# ASIC-Board.net
KiCad netlist of a schematic drawn in Altium Designer
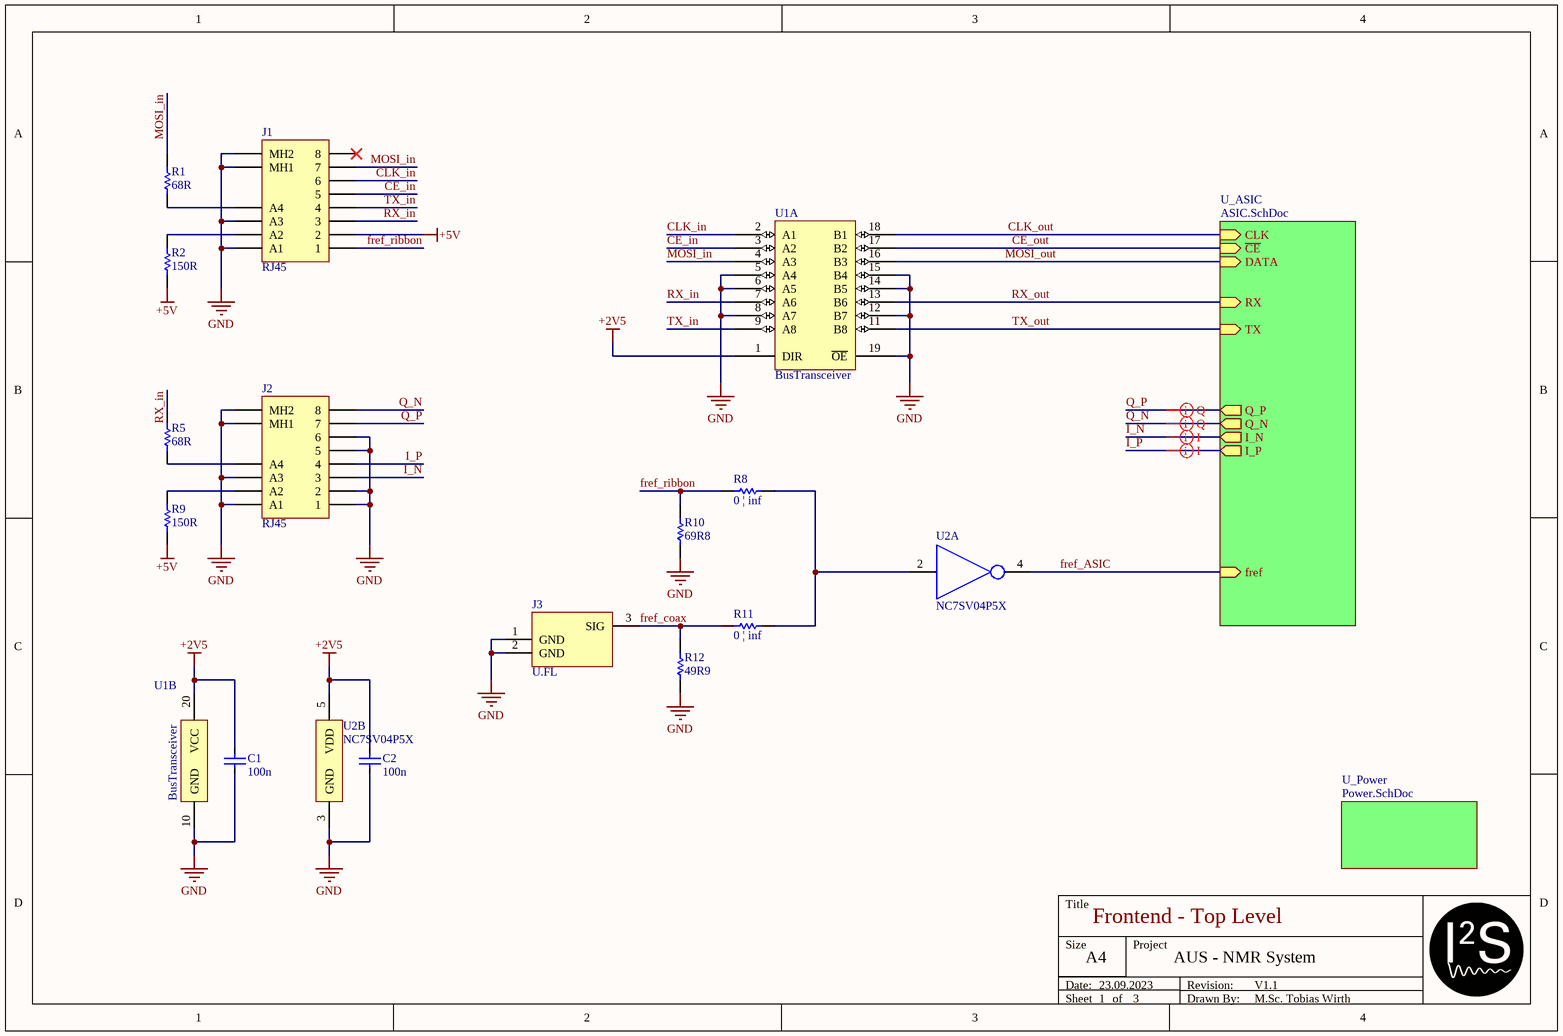
[diagram p0: ASIC-Board.SchDoc]

(export (version "E")
  (design (tool "Eeschema 10.0.6"))
  (components
    (comp (ref "C1") (value "100n") (footprint "CAP_0402") (libsource (lib "IIS-Lib_TW") (part "Cap")))
    (comp (ref "C2") (value "100n") (footprint "CAP_0402") (libsource (lib "IIS-Lib_TW") (part "Cap")))
    (comp (ref "J1")
      (value "RJ45")
      (footprint "RJ45 - RJE3A1880412")
      (description "Ethernet Connectors RJ45 SMT")
      (libsource (lib "IIS-Lib_TW") (part "RJ45"))
    )
    (comp (ref "J2")
      (value "RJ45")
      (footprint "RJ45 - RJE3A1880412")
      (description "Ethernet Connectors RJ45 SMT")
      (libsource (lib "IIS-Lib_TW") (part "RJ45"))
    )
    (comp (ref "J3") (value "U.FL") (footprint "U.FL") (libsource (lib "IIS-Lib_TW") (part "U.FL")))
    (comp (ref "R1") (value "68R") (footprint "RES_0603") (libsource (lib "IIS-Lib_TW") (part "Res")))
    (comp (ref "R2") (value "150R") (footprint "RES_0603") (libsource (lib "IIS-Lib_TW") (part "Res")))
    (comp (ref "R5") (value "68R") (footprint "RES_0603") (libsource (lib "IIS-Lib_TW") (part "Res")))
    (comp (ref "R8") (value "0 ¦ inf") (footprint "RES_0402") (libsource (lib "IIS-Lib_TW") (part "Res")))
    (comp (ref "R9") (value "150R") (footprint "RES_0603") (libsource (lib "IIS-Lib_TW") (part "Res")))
    (comp (ref "R10") (value "69R8") (footprint "RES_0402") (libsource (lib "IIS-Lib_TW") (part "Res")))
    (comp (ref "R11") (value "0 ¦ inf") (footprint "RES_0402") (libsource (lib "IIS-Lib_TW") (part "Res")))
    (comp (ref "R12") (value "49R9") (footprint "RES_0402") (libsource (lib "IIS-Lib_TW") (part "Res")))
    (comp (ref "U1")
      (value "BusTransceiver")
      (footprint "TSSOP-20")
      (libsource (lib "IIS-Lib_TW") (part "74LVC245A"))
    )
    (comp (ref "U2")
      (value "NC7SV04P5X")
      (footprint "SOT23-65P210X110-5N")
      (libsource (lib "IIS-Lib_TW") (part "NC7SV04P5X"))
    )
  )
  (nets
    (net (code "1") (name "+2V5") (class "Default")
      (node (ref "C1") (pin "1") (pinfunction "1_1") (pintype "passive"))
      (node (ref "C2") (pin "1") (pinfunction "1_1") (pintype "passive"))
      (node (ref "U1") (pin "1") (pinfunction "DIR_1") (pintype "passive"))
      (node (ref "U1") (pin "20") (pinfunction "VCC_20") (pintype "passive"))
      (node (ref "U2") (pin "5") (pinfunction "VDD_5") (pintype "passive"))
    )
    (net (code "2") (name "+5V") (class "Default")
      (node (ref "J1") (pin "2") (pinfunction "2_2") (pintype "passive"))
      (node (ref "R2") (pin "2") (pinfunction "2_2") (pintype "passive"))
      (node (ref "R9") (pin "2") (pinfunction "2_2") (pintype "passive"))
    )
    (net (code "3") (name "/CE_in") (class "Default")
      (node (ref "J1") (pin "5") (pinfunction "5_5") (pintype "passive"))
      (node (ref "U1") (pin "3") (pinfunction "A2_3") (pintype "bidirectional"))
    )
    (net (code "4") (name "/CE_out") (class "Default")
      (node (ref "U1") (pin "17") (pinfunction "B2_17") (pintype "bidirectional"))
    )
    (net (code "5") (name "/CLK_in") (class "Default")
      (node (ref "J1") (pin "6") (pinfunction "6_6") (pintype "passive"))
      (node (ref "U1") (pin "2") (pinfunction "A1_2") (pintype "bidirectional"))
    )
    (net (code "6") (name "/CLK_out") (class "Default")
      (node (ref "U1") (pin "18") (pinfunction "B1_18") (pintype "bidirectional"))
    )
    (net (code "7") (name "/I_N") (class "Default")
      (node (ref "J2") (pin "3") (pinfunction "3_3") (pintype "passive"))
    )
    (net (code "8") (name "/I_P") (class "Default")
      (node (ref "J2") (pin "4") (pinfunction "4_4") (pintype "passive"))
    )
    (net (code "9") (name "/MOSI_in") (class "Default")
      (node (ref "J1") (pin "7") (pinfunction "7_7") (pintype "passive"))
      (node (ref "R1") (pin "1") (pinfunction "1_1") (pintype "passive"))
      (node (ref "U1") (pin "4") (pinfunction "A3_4") (pintype "bidirectional"))
    )
    (net (code "10") (name "/MOSI_out") (class "Default")
      (node (ref "U1") (pin "16") (pinfunction "B3_16") (pintype "bidirectional"))
    )
    (net (code "11") (name "/Q_N") (class "Default")
      (node (ref "J2") (pin "8") (pinfunction "8_8") (pintype "passive"))
    )
    (net (code "12") (name "/Q_P") (class "Default")
      (node (ref "J2") (pin "7") (pinfunction "7_7") (pintype "passive"))
    )
    (net (code "13") (name "/RX_in") (class "Default")
      (node (ref "J1") (pin "3") (pinfunction "3_3") (pintype "passive"))
      (node (ref "R5") (pin "1") (pinfunction "1_1") (pintype "passive"))
      (node (ref "U1") (pin "7") (pinfunction "A6_7") (pintype "bidirectional"))
    )
    (net (code "14") (name "/RX_out") (class "Default")
      (node (ref "U1") (pin "13") (pinfunction "B6_13") (pintype "bidirectional"))
    )
    (net (code "15") (name "/TX_in") (class "Default")
      (node (ref "J1") (pin "4") (pinfunction "4_4") (pintype "passive"))
      (node (ref "U1") (pin "9") (pinfunction "A8_9") (pintype "bidirectional"))
    )
    (net (code "16") (name "/TX_out") (class "Default")
      (node (ref "U1") (pin "11") (pinfunction "B8_11") (pintype "bidirectional"))
    )
    (net (code "17") (name "/fref_ASIC") (class "Default")
      (node (ref "U2") (pin "4") (pinfunction "4_4") (pintype "passive"))
    )
    (net (code "18") (name "/fref_coax") (class "Default")
      (node (ref "J3") (pin "3") (pinfunction "SIG_3") (pintype "passive"))
      (node (ref "R11") (pin "2") (pinfunction "2_2") (pintype "passive"))
      (node (ref "R12") (pin "2") (pinfunction "2_2") (pintype "passive"))
    )
    (net (code "19") (name "/fref_ribbon") (class "Default")
      (node (ref "J1") (pin "1") (pinfunction "1_1") (pintype "passive"))
      (node (ref "R10") (pin "2") (pinfunction "2_2") (pintype "passive"))
      (node (ref "R8") (pin "2") (pinfunction "2_2") (pintype "passive"))
    )
    (net (code "20") (name "GND") (class "Default")
      (node (ref "C1") (pin "2") (pinfunction "2_2") (pintype "passive"))
      (node (ref "C2") (pin "2") (pinfunction "2_2") (pintype "passive"))
      (node (ref "J1") (pin "A1") (pinfunction "A1_A1") (pintype "passive"))
      (node (ref "J1") (pin "A3") (pinfunction "A3_A3") (pintype "passive"))
      (node (ref "J1") (pin "MH1") (pinfunction "MH1_MH1") (pintype "passive"))
      (node (ref "J1") (pin "MH2") (pinfunction "MH2_MH2") (pintype "passive"))
      (node (ref "J2") (pin "1") (pinfunction "1_1") (pintype "passive"))
      (node (ref "J2") (pin "2") (pinfunction "2_2") (pintype "passive"))
      (node (ref "J2") (pin "5") (pinfunction "5_5") (pintype "passive"))
      (node (ref "J2") (pin "6") (pinfunction "6_6") (pintype "passive"))
      (node (ref "J2") (pin "A1") (pinfunction "A1_A1") (pintype "passive"))
      (node (ref "J2") (pin "A3") (pinfunction "A3_A3") (pintype "passive"))
      (node (ref "J2") (pin "MH1") (pinfunction "MH1_MH1") (pintype "passive"))
      (node (ref "J2") (pin "MH2") (pinfunction "MH2_MH2") (pintype "passive"))
      (node (ref "J3") (pin "1") (pinfunction "GND_1") (pintype "passive"))
      (node (ref "J3") (pin "2") (pinfunction "GND_2") (pintype "passive"))
      (node (ref "R10") (pin "1") (pinfunction "1_1") (pintype "passive"))
      (node (ref "R12") (pin "1") (pinfunction "1_1") (pintype "passive"))
      (node (ref "U1") (pin "10") (pinfunction "GND_10") (pintype "passive"))
      (node (ref "U1") (pin "12") (pinfunction "B7_12") (pintype "bidirectional"))
      (node (ref "U1") (pin "14") (pinfunction "B5_14") (pintype "bidirectional"))
      (node (ref "U1") (pin "15") (pinfunction "B4_15") (pintype "bidirectional"))
      (node (ref "U1") (pin "19") (pinfunction "~{OE}_19") (pintype "passive"))
      (node (ref "U1") (pin "5") (pinfunction "A4_5") (pintype "bidirectional"))
      (node (ref "U1") (pin "6") (pinfunction "A5_6") (pintype "bidirectional"))
      (node (ref "U1") (pin "8") (pinfunction "A7_8") (pintype "bidirectional"))
      (node (ref "U2") (pin "3") (pinfunction "GND_3") (pintype "passive"))
    )
    (net (code "21") (name "Net-(J1-PadA2)") (class "Default")
      (node (ref "J1") (pin "A2") (pinfunction "A2_A2") (pintype "passive"))
      (node (ref "R2") (pin "1") (pinfunction "1_1") (pintype "passive"))
    )
    (net (code "22") (name "Net-(J1-PadA4)") (class "Default")
      (node (ref "J1") (pin "A4") (pinfunction "A4_A4") (pintype "passive"))
      (node (ref "R1") (pin "2") (pinfunction "2_2") (pintype "passive"))
    )
    (net (code "23") (name "Net-(J2-PadA2)") (class "Default")
      (node (ref "J2") (pin "A2") (pinfunction "A2_A2") (pintype "passive"))
      (node (ref "R9") (pin "1") (pinfunction "1_1") (pintype "passive"))
    )
    (net (code "24") (name "Net-(J2-PadA4)") (class "Default")
      (node (ref "J2") (pin "A4") (pinfunction "A4_A4") (pintype "passive"))
      (node (ref "R5") (pin "2") (pinfunction "2_2") (pintype "passive"))
    )
    (net (code "25") (name "Net-(R11-Pad1)") (class "Default")
      (node (ref "R11") (pin "1") (pinfunction "1_1") (pintype "passive"))
      (node (ref "R8") (pin "1") (pinfunction "1_1") (pintype "passive"))
      (node (ref "U2") (pin "2") (pinfunction "2_2") (pintype "passive"))
    )
    (net (code "26") (name "unconnected-(J1-Pad8)") (class "Default")
      (node (ref "J1") (pin "8") (pinfunction "8_8") (pintype "passive+no_connect"))
    )
  )
)
